# 411Level1.net
KiCad netlist of a schematic drawn in EAGLE
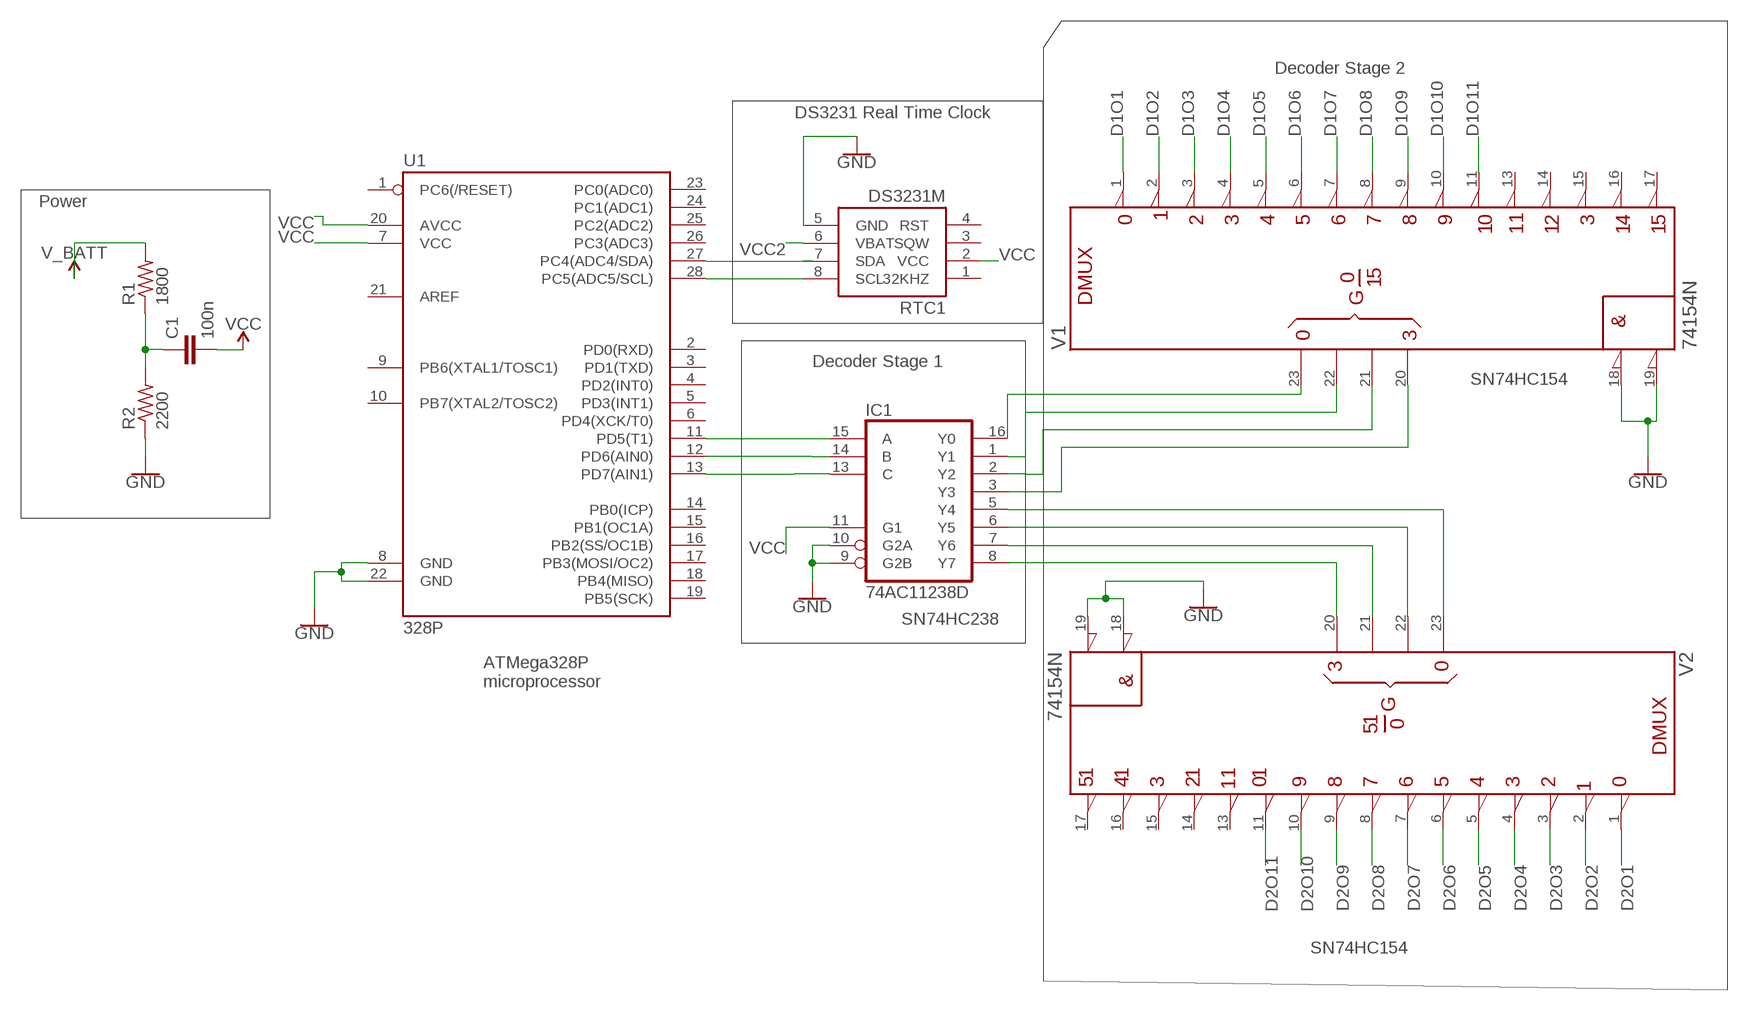
[diagram p0: schematic, sheet 1]
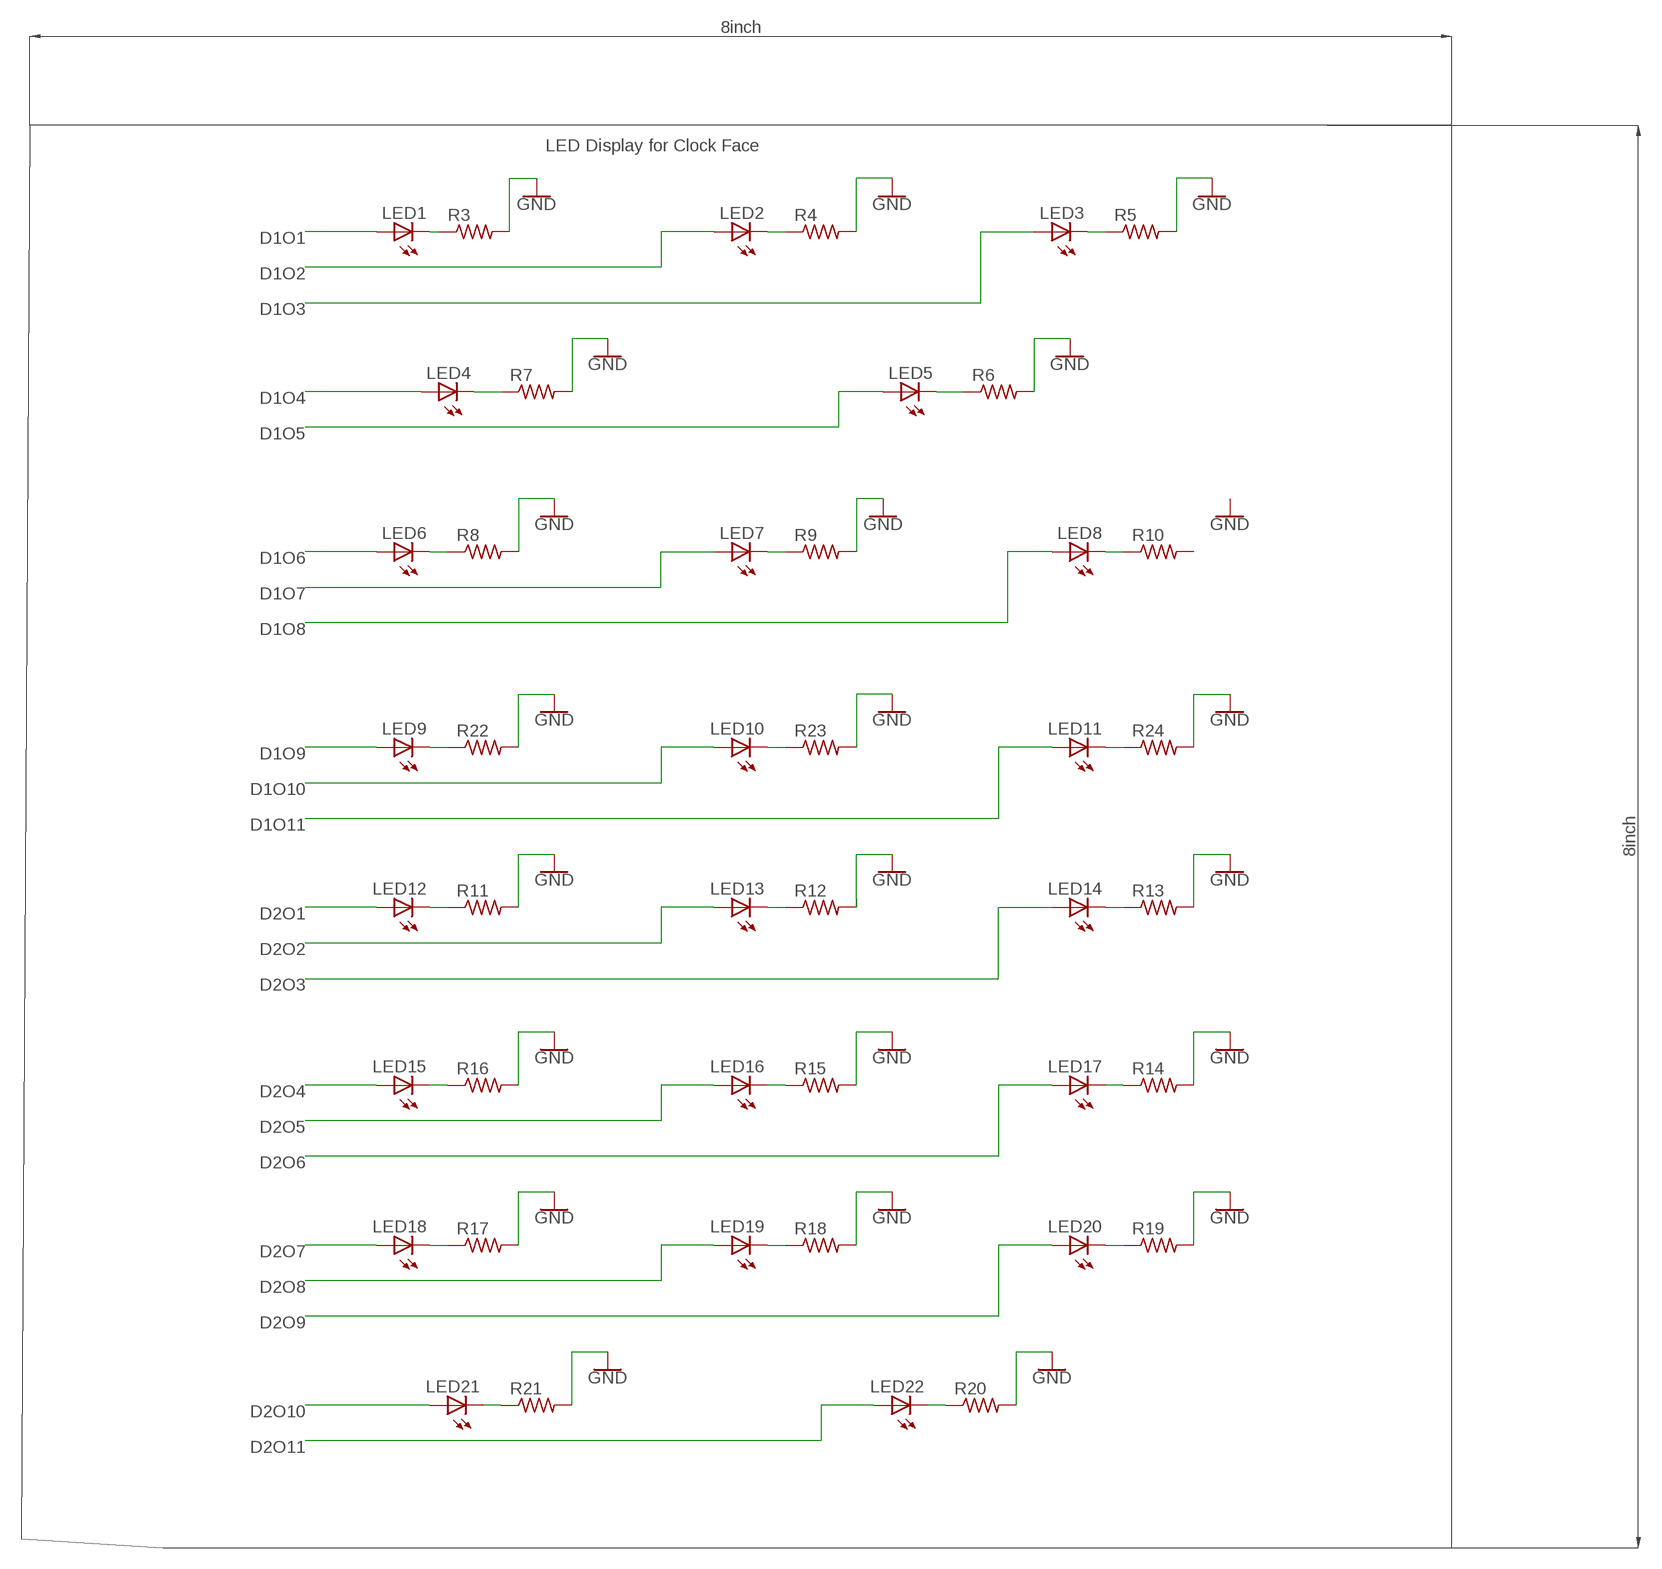
[diagram p1: schematic, sheet 2]

(export (version "E")
  (design (tool "Eeschema 10.0.6"))
  (components
    (comp (ref "C1")
      (value "100n")
      (footprint "eagle-import:C025-025X050")
      (libsource (lib "eagle-import") (part "C-EU025-025X050"))
    )
    (comp (ref "IC1")
      (value "74AC11238D")
      (footprint "eagle-import:SO16")
      (libsource (lib "eagle-import") (part "74AC11238D"))
    )
    (comp (ref "R1")
      (value "1800")
      (footprint "eagle-import:0204V")
      (libsource (lib "eagle-import") (part "R-US_0204/2V"))
    )
    (comp (ref "R2")
      (value "2200")
      (footprint "eagle-import:0204V")
      (libsource (lib "eagle-import") (part "R-US_0204/2V"))
    )
    (comp (ref "RTC1")
      (value "DS3231M")
      (footprint "eagle-import:SO08")
      (libsource (lib "eagle-import") (part "DS3231M"))
    )
    (comp (ref "U1")
      (value "328P")
      (footprint "eagle-import:DIP28")
      (libsource (lib "eagle-import") (part "ATMEGA328P_PDIP"))
    )
    (comp (ref "V1")
      (value "74154N")
      (footprint "eagle-import:DIL24-3")
      (libsource (lib "eagle-import") (part "74154N"))
    )
    (comp (ref "V2")
      (value "74154N")
      (footprint "eagle-import:DIL24-3")
      (libsource (lib "eagle-import") (part "74154N"))
    )
    (comp (ref "LED1")
      (value "LED5MM")
      (footprint "eagle-import:LED5MM")
      (libsource (lib "eagle-import") (part "LED5MM"))
    )
    (comp (ref "LED2")
      (value "LED5MM")
      (footprint "eagle-import:LED5MM")
      (libsource (lib "eagle-import") (part "LED5MM"))
    )
    (comp (ref "LED3")
      (value "LED5MM")
      (footprint "eagle-import:LED5MM")
      (libsource (lib "eagle-import") (part "LED5MM"))
    )
    (comp (ref "LED4")
      (value "LED5MM")
      (footprint "eagle-import:LED5MM")
      (libsource (lib "eagle-import") (part "LED5MM"))
    )
    (comp (ref "LED5")
      (value "LED5MM")
      (footprint "eagle-import:LED5MM")
      (libsource (lib "eagle-import") (part "LED5MM"))
    )
    (comp (ref "LED6")
      (value "LED5MM")
      (footprint "eagle-import:LED5MM")
      (libsource (lib "eagle-import") (part "LED5MM"))
    )
    (comp (ref "LED7")
      (value "LED5MM")
      (footprint "eagle-import:LED5MM")
      (libsource (lib "eagle-import") (part "LED5MM"))
    )
    (comp (ref "LED8")
      (value "LED5MM")
      (footprint "eagle-import:LED5MM")
      (libsource (lib "eagle-import") (part "LED5MM"))
    )
    (comp (ref "LED9")
      (value "LED5MM")
      (footprint "eagle-import:LED5MM")
      (libsource (lib "eagle-import") (part "LED5MM"))
    )
    (comp (ref "LED10")
      (value "LED5MM")
      (footprint "eagle-import:LED5MM")
      (libsource (lib "eagle-import") (part "LED5MM"))
    )
    (comp (ref "LED11")
      (value "LED5MM")
      (footprint "eagle-import:LED5MM")
      (libsource (lib "eagle-import") (part "LED5MM"))
    )
    (comp (ref "LED12")
      (value "LED5MM")
      (footprint "eagle-import:LED5MM")
      (libsource (lib "eagle-import") (part "LED5MM"))
    )
    (comp (ref "LED13")
      (value "LED5MM")
      (footprint "eagle-import:LED5MM")
      (libsource (lib "eagle-import") (part "LED5MM"))
    )
    (comp (ref "LED14")
      (value "LED5MM")
      (footprint "eagle-import:LED5MM")
      (libsource (lib "eagle-import") (part "LED5MM"))
    )
    (comp (ref "LED15")
      (value "LED5MM")
      (footprint "eagle-import:LED5MM")
      (libsource (lib "eagle-import") (part "LED5MM"))
    )
    (comp (ref "LED16")
      (value "LED5MM")
      (footprint "eagle-import:LED5MM")
      (libsource (lib "eagle-import") (part "LED5MM"))
    )
    (comp (ref "LED17")
      (value "LED5MM")
      (footprint "eagle-import:LED5MM")
      (libsource (lib "eagle-import") (part "LED5MM"))
    )
    (comp (ref "LED18")
      (value "LED5MM")
      (footprint "eagle-import:LED5MM")
      (libsource (lib "eagle-import") (part "LED5MM"))
    )
    (comp (ref "LED19")
      (value "LED5MM")
      (footprint "eagle-import:LED5MM")
      (libsource (lib "eagle-import") (part "LED5MM"))
    )
    (comp (ref "LED20")
      (value "LED5MM")
      (footprint "eagle-import:LED5MM")
      (libsource (lib "eagle-import") (part "LED5MM"))
    )
    (comp (ref "LED21")
      (value "LED5MM")
      (footprint "eagle-import:LED5MM")
      (libsource (lib "eagle-import") (part "LED5MM"))
    )
    (comp (ref "LED22")
      (value "LED5MM")
      (footprint "eagle-import:LED5MM")
      (libsource (lib "eagle-import") (part "LED5MM"))
    )
    (comp (ref "R3")
      (value "R-US_0204/5")
      (footprint "eagle-import:0204_5")
      (libsource (lib "eagle-import") (part "R-US_0204/5"))
    )
    (comp (ref "R4")
      (value "R-US_0204/5")
      (footprint "eagle-import:0204_5")
      (libsource (lib "eagle-import") (part "R-US_0204/5"))
    )
    (comp (ref "R5")
      (value "R-US_0204/5")
      (footprint "eagle-import:0204_5")
      (libsource (lib "eagle-import") (part "R-US_0204/5"))
    )
    (comp (ref "R6")
      (value "R-US_0204/5")
      (footprint "eagle-import:0204_5")
      (libsource (lib "eagle-import") (part "R-US_0204/5"))
    )
    (comp (ref "R7")
      (value "R-US_0204/5")
      (footprint "eagle-import:0204_5")
      (libsource (lib "eagle-import") (part "R-US_0204/5"))
    )
    (comp (ref "R8")
      (value "R-US_0204/5")
      (footprint "eagle-import:0204_5")
      (libsource (lib "eagle-import") (part "R-US_0204/5"))
    )
    (comp (ref "R9")
      (value "R-US_0204/5")
      (footprint "eagle-import:0204_5")
      (libsource (lib "eagle-import") (part "R-US_0204/5"))
    )
    (comp (ref "R10")
      (value "R-US_0204/5")
      (footprint "eagle-import:0204_5")
      (libsource (lib "eagle-import") (part "R-US_0204/5"))
    )
    (comp (ref "R11")
      (value "R-US_0204/5")
      (footprint "eagle-import:0204_5")
      (libsource (lib "eagle-import") (part "R-US_0204/5"))
    )
    (comp (ref "R12")
      (value "R-US_0204/5")
      (footprint "eagle-import:0204_5")
      (libsource (lib "eagle-import") (part "R-US_0204/5"))
    )
    (comp (ref "R13")
      (value "R-US_0204/5")
      (footprint "eagle-import:0204_5")
      (libsource (lib "eagle-import") (part "R-US_0204/5"))
    )
    (comp (ref "R14")
      (value "R-US_0204/5")
      (footprint "eagle-import:0204_5")
      (libsource (lib "eagle-import") (part "R-US_0204/5"))
    )
    (comp (ref "R15")
      (value "R-US_0204/5")
      (footprint "eagle-import:0204_5")
      (libsource (lib "eagle-import") (part "R-US_0204/5"))
    )
    (comp (ref "R16")
      (value "R-US_0204/5")
      (footprint "eagle-import:0204_5")
      (libsource (lib "eagle-import") (part "R-US_0204/5"))
    )
    (comp (ref "R17")
      (value "R-US_0204/5")
      (footprint "eagle-import:0204_5")
      (libsource (lib "eagle-import") (part "R-US_0204/5"))
    )
    (comp (ref "R18")
      (value "R-US_0204/5")
      (footprint "eagle-import:0204_5")
      (libsource (lib "eagle-import") (part "R-US_0204/5"))
    )
    (comp (ref "R19")
      (value "R-US_0204/5")
      (footprint "eagle-import:0204_5")
      (libsource (lib "eagle-import") (part "R-US_0204/5"))
    )
    (comp (ref "R20")
      (value "R-US_0204/5")
      (footprint "eagle-import:0204_5")
      (libsource (lib "eagle-import") (part "R-US_0204/5"))
    )
    (comp (ref "R21")
      (value "R-US_0204/5")
      (footprint "eagle-import:0204_5")
      (libsource (lib "eagle-import") (part "R-US_0204/5"))
    )
    (comp (ref "R22")
      (value "R-US_0204/5")
      (footprint "eagle-import:0204_5")
      (libsource (lib "eagle-import") (part "R-US_0204/5"))
    )
    (comp (ref "R23")
      (value "R-US_0204/5")
      (footprint "eagle-import:0204_5")
      (libsource (lib "eagle-import") (part "R-US_0204/5"))
    )
    (comp (ref "R24")
      (value "R-US_0204/5")
      (footprint "eagle-import:0204_5")
      (libsource (lib "eagle-import") (part "R-US_0204/5"))
    )
  )
  (nets
    (net (code "1") (name "D1O1") (class "Default")
      (node (ref "LED1") (pin "A") (pinfunction "A_A") (pintype "passive"))
      (node (ref "V1") (pin "1") (pinfunction "0_1") (pintype "output"))
    )
    (net (code "2") (name "D1O2") (class "Default")
      (node (ref "LED2") (pin "A") (pinfunction "A_A") (pintype "passive"))
      (node (ref "V1") (pin "2") (pinfunction "1_2") (pintype "output"))
    )
    (net (code "3") (name "D1O3") (class "Default")
      (node (ref "LED3") (pin "A") (pinfunction "A_A") (pintype "passive"))
      (node (ref "V1") (pin "3") (pinfunction "2_3") (pintype "output"))
    )
    (net (code "4") (name "D1O4") (class "Default")
      (node (ref "LED4") (pin "A") (pinfunction "A_A") (pintype "passive"))
      (node (ref "V1") (pin "4") (pinfunction "3_4") (pintype "output"))
    )
    (net (code "5") (name "D1O5") (class "Default")
      (node (ref "LED5") (pin "A") (pinfunction "A_A") (pintype "passive"))
      (node (ref "V1") (pin "5") (pinfunction "4_5") (pintype "output"))
    )
    (net (code "6") (name "D1O6") (class "Default")
      (node (ref "LED6") (pin "A") (pinfunction "A_A") (pintype "passive"))
      (node (ref "V1") (pin "6") (pinfunction "5_6") (pintype "output"))
    )
    (net (code "7") (name "D1O7") (class "Default")
      (node (ref "LED7") (pin "A") (pinfunction "A_A") (pintype "passive"))
      (node (ref "V1") (pin "7") (pinfunction "6_7") (pintype "output"))
    )
    (net (code "8") (name "D1O8") (class "Default")
      (node (ref "LED8") (pin "A") (pinfunction "A_A") (pintype "passive"))
      (node (ref "V1") (pin "8") (pinfunction "7_8") (pintype "output"))
    )
    (net (code "9") (name "D1O9") (class "Default")
      (node (ref "LED9") (pin "A") (pinfunction "A_A") (pintype "passive"))
      (node (ref "V1") (pin "9") (pinfunction "8_9") (pintype "output"))
    )
    (net (code "10") (name "D1O10") (class "Default")
      (node (ref "LED10") (pin "A") (pinfunction "A_A") (pintype "passive"))
      (node (ref "V1") (pin "10") (pinfunction "9_10") (pintype "output"))
    )
    (net (code "11") (name "D1O11") (class "Default")
      (node (ref "LED11") (pin "A") (pinfunction "A_A") (pintype "passive"))
      (node (ref "V1") (pin "11") (pinfunction "10_11") (pintype "output"))
    )
    (net (code "12") (name "D2O1") (class "Default")
      (node (ref "LED12") (pin "A") (pinfunction "A_A") (pintype "passive"))
      (node (ref "V2") (pin "1") (pinfunction "0_1") (pintype "output"))
    )
    (net (code "13") (name "D2O2") (class "Default")
      (node (ref "LED13") (pin "A") (pinfunction "A_A") (pintype "passive"))
      (node (ref "V2") (pin "2") (pinfunction "1_2") (pintype "output"))
    )
    (net (code "14") (name "D2O3") (class "Default")
      (node (ref "LED14") (pin "A") (pinfunction "A_A") (pintype "passive"))
      (node (ref "V2") (pin "3") (pinfunction "2_3") (pintype "output"))
    )
    (net (code "15") (name "D2O4") (class "Default")
      (node (ref "LED15") (pin "A") (pinfunction "A_A") (pintype "passive"))
      (node (ref "V2") (pin "4") (pinfunction "3_4") (pintype "output"))
    )
    (net (code "16") (name "D2O5") (class "Default")
      (node (ref "LED16") (pin "A") (pinfunction "A_A") (pintype "passive"))
      (node (ref "V2") (pin "5") (pinfunction "4_5") (pintype "output"))
    )
    (net (code "17") (name "D2O6") (class "Default")
      (node (ref "LED17") (pin "A") (pinfunction "A_A") (pintype "passive"))
      (node (ref "V2") (pin "6") (pinfunction "5_6") (pintype "output"))
    )
    (net (code "18") (name "D2O7") (class "Default")
      (node (ref "LED18") (pin "A") (pinfunction "A_A") (pintype "passive"))
      (node (ref "V2") (pin "7") (pinfunction "6_7") (pintype "output"))
    )
    (net (code "19") (name "D2O8") (class "Default")
      (node (ref "LED19") (pin "A") (pinfunction "A_A") (pintype "passive"))
      (node (ref "V2") (pin "8") (pinfunction "7_8") (pintype "output"))
    )
    (net (code "20") (name "D2O9") (class "Default")
      (node (ref "LED20") (pin "A") (pinfunction "A_A") (pintype "passive"))
      (node (ref "V2") (pin "9") (pinfunction "8_9") (pintype "output"))
    )
    (net (code "21") (name "D2O10") (class "Default")
      (node (ref "LED21") (pin "A") (pinfunction "A_A") (pintype "passive"))
      (node (ref "V2") (pin "10") (pinfunction "9_10") (pintype "output"))
    )
    (net (code "22") (name "D2O11") (class "Default")
      (node (ref "LED22") (pin "A") (pinfunction "A_A") (pintype "passive"))
      (node (ref "V2") (pin "11") (pinfunction "10_11") (pintype "output"))
    )
    (net (code "23") (name "GND") (class "Default")
      (node (ref "IC1") (pin "10") (pinfunction "G2A_10") (pintype "input"))
      (node (ref "IC1") (pin "9") (pinfunction "G2B_9") (pintype "input"))
      (node (ref "R11") (pin "2") (pinfunction "2_2") (pintype "passive"))
      (node (ref "R12") (pin "2") (pinfunction "2_2") (pintype "passive"))
      (node (ref "R13") (pin "2") (pinfunction "2_2") (pintype "passive"))
      (node (ref "R14") (pin "2") (pinfunction "2_2") (pintype "passive"))
      (node (ref "R15") (pin "2") (pinfunction "2_2") (pintype "passive"))
      (node (ref "R16") (pin "2") (pinfunction "2_2") (pintype "passive"))
      (node (ref "R17") (pin "2") (pinfunction "2_2") (pintype "passive"))
      (node (ref "R18") (pin "2") (pinfunction "2_2") (pintype "passive"))
      (node (ref "R19") (pin "2") (pinfunction "2_2") (pintype "passive"))
      (node (ref "R2") (pin "1") (pinfunction "1_1") (pintype "passive"))
      (node (ref "R20") (pin "2") (pinfunction "2_2") (pintype "passive"))
      (node (ref "R21") (pin "2") (pinfunction "2_2") (pintype "passive"))
      (node (ref "R22") (pin "2") (pinfunction "2_2") (pintype "passive"))
      (node (ref "R23") (pin "2") (pinfunction "2_2") (pintype "passive"))
      (node (ref "R24") (pin "2") (pinfunction "2_2") (pintype "passive"))
      (node (ref "R3") (pin "2") (pinfunction "2_2") (pintype "passive"))
      (node (ref "R4") (pin "2") (pinfunction "2_2") (pintype "passive"))
      (node (ref "R5") (pin "2") (pinfunction "2_2") (pintype "passive"))
      (node (ref "R6") (pin "2") (pinfunction "2_2") (pintype "passive"))
      (node (ref "R7") (pin "2") (pinfunction "2_2") (pintype "passive"))
      (node (ref "R8") (pin "2") (pinfunction "2_2") (pintype "passive"))
      (node (ref "R9") (pin "2") (pinfunction "2_2") (pintype "passive"))
      (node (ref "RTC1") (pin "5") (pinfunction "GND_5") (pintype "power_in"))
      (node (ref "U1") (pin "22") (pinfunction "GND_22") (pintype "bidirectional"))
      (node (ref "U1") (pin "8") (pinfunction "GND_8") (pintype "bidirectional"))
      (node (ref "V1") (pin "18") (pinfunction "~{G1}_18") (pintype "input"))
      (node (ref "V1") (pin "19") (pinfunction "~{G2}_19") (pintype "input"))
      (node (ref "V2") (pin "18") (pinfunction "~{G1}_18") (pintype "input"))
      (node (ref "V2") (pin "19") (pinfunction "~{G2}_19") (pintype "input"))
    )
    (net (code "24") (name "Net-(C1-Pad1)") (class "Default")
      (node (ref "C1") (pin "1") (pinfunction "1_1") (pintype "passive"))
      (node (ref "R1") (pin "1") (pinfunction "1_1") (pintype "passive"))
      (node (ref "R2") (pin "2") (pinfunction "2_2") (pintype "passive"))
    )
    (net (code "25") (name "Net-(IC1A-A)") (class "Default")
      (node (ref "IC1") (pin "15") (pinfunction "A_15") (pintype "input"))
      (node (ref "U1") (pin "11") (pinfunction "PD5(T1)_11") (pintype "bidirectional"))
    )
    (net (code "26") (name "Net-(IC1A-B)") (class "Default")
      (node (ref "IC1") (pin "14") (pinfunction "B_14") (pintype "input"))
      (node (ref "U1") (pin "12") (pinfunction "PD6(AIN0)_12") (pintype "bidirectional"))
    )
    (net (code "27") (name "Net-(IC1A-C)") (class "Default")
      (node (ref "IC1") (pin "13") (pinfunction "C_13") (pintype "input"))
      (node (ref "U1") (pin "13") (pinfunction "PD7(AIN1)_13") (pintype "bidirectional"))
    )
    (net (code "28") (name "Net-(IC1A-Y0)") (class "Default")
      (node (ref "IC1") (pin "16") (pinfunction "Y0_16") (pintype "output"))
      (node (ref "V1") (pin "23") (pinfunction "A_23") (pintype "input"))
    )
    (net (code "29") (name "Net-(IC1A-Y1)") (class "Default")
      (node (ref "IC1") (pin "1") (pinfunction "Y1_1") (pintype "output"))
      (node (ref "V1") (pin "22") (pinfunction "B_22") (pintype "input"))
    )
    (net (code "30") (name "Net-(IC1A-Y2)") (class "Default")
      (node (ref "IC1") (pin "2") (pinfunction "Y2_2") (pintype "output"))
      (node (ref "V1") (pin "21") (pinfunction "C_21") (pintype "input"))
    )
    (net (code "31") (name "Net-(IC1A-Y3)") (class "Default")
      (node (ref "IC1") (pin "3") (pinfunction "Y3_3") (pintype "output"))
      (node (ref "V1") (pin "20") (pinfunction "D_20") (pintype "input"))
    )
    (net (code "32") (name "Net-(IC1A-Y4)") (class "Default")
      (node (ref "IC1") (pin "5") (pinfunction "Y4_5") (pintype "output"))
      (node (ref "V2") (pin "23") (pinfunction "A_23") (pintype "input"))
    )
    (net (code "33") (name "Net-(IC1A-Y5)") (class "Default")
      (node (ref "IC1") (pin "6") (pinfunction "Y5_6") (pintype "output"))
      (node (ref "V2") (pin "22") (pinfunction "B_22") (pintype "input"))
    )
    (net (code "34") (name "Net-(IC1A-Y6)") (class "Default")
      (node (ref "IC1") (pin "7") (pinfunction "Y6_7") (pintype "output"))
      (node (ref "V2") (pin "21") (pinfunction "C_21") (pintype "input"))
    )
    (net (code "35") (name "Net-(IC1A-Y7)") (class "Default")
      (node (ref "IC1") (pin "8") (pinfunction "Y7_8") (pintype "output"))
      (node (ref "V2") (pin "20") (pinfunction "D_20") (pintype "input"))
    )
    (net (code "36") (name "Net-(LED1-C)") (class "Default")
      (node (ref "LED1") (pin "K") (pinfunction "C_K") (pintype "passive"))
      (node (ref "R3") (pin "1") (pinfunction "1_1") (pintype "passive"))
    )
    (net (code "37") (name "Net-(LED2-C)") (class "Default")
      (node (ref "LED2") (pin "K") (pinfunction "C_K") (pintype "passive"))
      (node (ref "R4") (pin "1") (pinfunction "1_1") (pintype "passive"))
    )
    (net (code "38") (name "Net-(LED3-C)") (class "Default")
      (node (ref "LED3") (pin "K") (pinfunction "C_K") (pintype "passive"))
      (node (ref "R5") (pin "1") (pinfunction "1_1") (pintype "passive"))
    )
    (net (code "39") (name "Net-(LED4-C)") (class "Default")
      (node (ref "LED4") (pin "K") (pinfunction "C_K") (pintype "passive"))
      (node (ref "R7") (pin "1") (pinfunction "1_1") (pintype "passive"))
    )
    (net (code "40") (name "Net-(LED5-C)") (class "Default")
      (node (ref "LED5") (pin "K") (pinfunction "C_K") (pintype "passive"))
      (node (ref "R6") (pin "1") (pinfunction "1_1") (pintype "passive"))
    )
    (net (code "41") (name "Net-(LED6-C)") (class "Default")
      (node (ref "LED6") (pin "K") (pinfunction "C_K") (pintype "passive"))
      (node (ref "R8") (pin "1") (pinfunction "1_1") (pintype "passive"))
    )
    (net (code "42") (name "Net-(LED7-C)") (class "Default")
      (node (ref "LED7") (pin "K") (pinfunction "C_K") (pintype "passive"))
      (node (ref "R9") (pin "1") (pinfunction "1_1") (pintype "passive"))
    )
    (net (code "43") (name "Net-(LED8-C)") (class "Default")
      (node (ref "LED8") (pin "K") (pinfunction "C_K") (pintype "passive"))
      (node (ref "R10") (pin "1") (pinfunction "1_1") (pintype "passive"))
    )
    (net (code "44") (name "Net-(LED9-C)") (class "Default")
      (node (ref "LED9") (pin "K") (pinfunction "C_K") (pintype "passive"))
      (node (ref "R22") (pin "1") (pinfunction "1_1") (pintype "passive"))
    )
    (net (code "45") (name "Net-(LED10-C)") (class "Default")
      (node (ref "LED10") (pin "K") (pinfunction "C_K") (pintype "passive"))
      (node (ref "R23") (pin "1") (pinfunction "1_1") (pintype "passive"))
    )
    (net (code "46") (name "Net-(LED11-C)") (class "Default")
      (node (ref "LED11") (pin "K") (pinfunction "C_K") (pintype "passive"))
      (node (ref "R24") (pin "1") (pinfunction "1_1") (pintype "passive"))
    )
    (net (code "47") (name "Net-(LED12-C)") (class "Default")
      (node (ref "LED12") (pin "K") (pinfunction "C_K") (pintype "passive"))
      (node (ref "R11") (pin "1") (pinfunction "1_1") (pintype "passive"))
    )
    (net (code "48") (name "Net-(LED13-C)") (class "Default")
      (node (ref "LED13") (pin "K") (pinfunction "C_K") (pintype "passive"))
      (node (ref "R12") (pin "1") (pinfunction "1_1") (pintype "passive"))
    )
    (net (code "49") (name "Net-(LED14-C)") (class "Default")
      (node (ref "LED14") (pin "K") (pinfunction "C_K") (pintype "passive"))
      (node (ref "R13") (pin "1") (pinfunction "1_1") (pintype "passive"))
    )
    (net (code "50") (name "Net-(LED15-C)") (class "Default")
      (node (ref "LED15") (pin "K") (pinfunction "C_K") (pintype "passive"))
      (node (ref "R16") (pin "1") (pinfunction "1_1") (pintype "passive"))
    )
    (net (code "51") (name "Net-(LED16-C)") (class "Default")
      (node (ref "LED16") (pin "K") (pinfunction "C_K") (pintype "passive"))
      (node (ref "R15") (pin "1") (pinfunction "1_1") (pintype "passive"))
    )
    (net (code "52") (name "Net-(LED17-C)") (class "Default")
      (node (ref "LED17") (pin "K") (pinfunction "C_K") (pintype "passive"))
      (node (ref "R14") (pin "1") (pinfunction "1_1") (pintype "passive"))
    )
    (net (code "53") (name "Net-(LED18-C)") (class "Default")
      (node (ref "LED18") (pin "K") (pinfunction "C_K") (pintype "passive"))
      (node (ref "R17") (pin "1") (pinfunction "1_1") (pintype "passive"))
    )
    (net (code "54") (name "Net-(LED19-C)") (class "Default")
      (node (ref "LED19") (pin "K") (pinfunction "C_K") (pintype "passive"))
      (node (ref "R18") (pin "1") (pinfunction "1_1") (pintype "passive"))
    )
    (net (code "55") (name "Net-(LED20-C)") (class "Default")
      (node (ref "LED20") (pin "K") (pinfunction "C_K") (pintype "passive"))
      (node (ref "R19") (pin "1") (pinfunction "1_1") (pintype "passive"))
    )
    (net (code "56") (name "Net-(LED21-C)") (class "Default")
      (node (ref "LED21") (pin "K") (pinfunction "C_K") (pintype "passive"))
      (node (ref "R21") (pin "1") (pinfunction "1_1") (pintype "passive"))
    )
    (net (code "57") (name "Net-(LED22-C)") (class "Default")
      (node (ref "LED22") (pin "K") (pinfunction "C_K") (pintype "passive"))
      (node (ref "R20") (pin "1") (pinfunction "1_1") (pintype "passive"))
    )
    (net (code "58") (name "Net-(RTC1-SCL)") (class "Default")
      (node (ref "RTC1") (pin "8") (pinfunction "SCL_8") (pintype "bidirectional"))
      (node (ref "U1") (pin "28") (pinfunction "PC5(ADC5/SCL)_28") (pintype "bidirectional"))
    )
    (net (code "59") (name "Net-(RTC1-SDA)") (class "Default")
      (node (ref "RTC1") (pin "7") (pinfunction "SDA_7") (pintype "bidirectional"))
      (node (ref "U1") (pin "27") (pinfunction "PC4(ADC4/SDA)_27") (pintype "bidirectional"))
    )
    (net (code "60") (name "VCC") (class "Default")
      (node (ref "C1") (pin "2") (pinfunction "2_2") (pintype "passive"))
      (node (ref "IC1") (pin "11") (pinfunction "G1_11") (pintype "input"))
      (node (ref "RTC1") (pin "2") (pinfunction "VCC_2") (pintype "power_in"))
      (node (ref "U1") (pin "20") (pinfunction "AVCC_20") (pintype "bidirectional"))
      (node (ref "U1") (pin "7") (pinfunction "VCC_7") (pintype "bidirectional"))
    )
    (net (code "61") (name "VCC2") (class "Default")
      (node (ref "RTC1") (pin "6") (pinfunction "VBAT_6") (pintype "power_in"))
    )
    (net (code "62") (name "V_BATT") (class "Default")
      (node (ref "R1") (pin "2") (pinfunction "2_2") (pintype "passive"))
    )
    (net (code "63") (name "unconnected-(R10-Pad2)") (class "Default")
      (node (ref "R10") (pin "2") (pinfunction "2_2") (pintype "passive"))
    )
    (net (code "64") (name "unconnected-(RTC1-32KHZ-Pad1)") (class "Default")
      (node (ref "RTC1") (pin "1") (pinfunction "32KHZ_1") (pintype "output"))
    )
    (net (code "65") (name "unconnected-(RTC1-RST-Pad4)") (class "Default")
      (node (ref "RTC1") (pin "4") (pinfunction "RST_4") (pintype "bidirectional"))
    )
    (net (code "66") (name "unconnected-(RTC1-SQW-Pad3)") (class "Default")
      (node (ref "RTC1") (pin "3") (pinfunction "SQW_3") (pintype "output"))
    )
    (net (code "67") (name "unconnected-(U1-AREF-Pad21)") (class "Default")
      (node (ref "U1") (pin "21") (pinfunction "AREF_21") (pintype "bidirectional"))
    )
    (net (code "68") (name "unconnected-(U1-PB0(ICP)-Pad14)") (class "Default")
      (node (ref "U1") (pin "14") (pinfunction "PB0(ICP)_14") (pintype "bidirectional"))
    )
    (net (code "69") (name "unconnected-(U1-PB1(OC1A)-Pad15)") (class "Default")
      (node (ref "U1") (pin "15") (pinfunction "PB1(OC1A)_15") (pintype "bidirectional"))
    )
    (net (code "70") (name "unconnected-(U1-PB2(SS{slash}OC1B)-Pad16)") (class "Default")
      (node (ref "U1") (pin "16") (pinfunction "PB2(SS/OC1B)_16") (pintype "bidirectional"))
    )
    (net (code "71") (name "unconnected-(U1-PB3(MOSI{slash}OC2)-Pad17)") (class "Default")
      (node (ref "U1") (pin "17") (pinfunction "PB3(MOSI/OC2)_17") (pintype "bidirectional"))
    )
    (net (code "72") (name "unconnected-(U1-PB4(MISO)-Pad18)") (class "Default")
      (node (ref "U1") (pin "18") (pinfunction "PB4(MISO)_18") (pintype "bidirectional"))
    )
    (net (code "73") (name "unconnected-(U1-PB5(SCK)-Pad19)") (class "Default")
      (node (ref "U1") (pin "19") (pinfunction "PB5(SCK)_19") (pintype "bidirectional"))
    )
    (net (code "74") (name "unconnected-(U1-PB6(XTAL1{slash}TOSC1)-Pad9)") (class "Default")
      (node (ref "U1") (pin "9") (pinfunction "PB6(XTAL1/TOSC1)_9") (pintype "bidirectional"))
    )
    (net (code "75") (name "unconnected-(U1-PB7(XTAL2{slash}TOSC2)-Pad10)") (class "Default")
      (node (ref "U1") (pin "10") (pinfunction "PB7(XTAL2/TOSC2)_10") (pintype "bidirectional"))
    )
    (net (code "76") (name "unconnected-(U1-PC0(ADC0)-Pad23)") (class "Default")
      (node (ref "U1") (pin "23") (pinfunction "PC0(ADC0)_23") (pintype "bidirectional"))
    )
    (net (code "77") (name "unconnected-(U1-PC1(ADC1)-Pad24)") (class "Default")
      (node (ref "U1") (pin "24") (pinfunction "PC1(ADC1)_24") (pintype "bidirectional"))
    )
    (net (code "78") (name "unconnected-(U1-PC2(ADC2)-Pad25)") (class "Default")
      (node (ref "U1") (pin "25") (pinfunction "PC2(ADC2)_25") (pintype "bidirectional"))
    )
    (net (code "79") (name "unconnected-(U1-PC3(ADC3)-Pad26)") (class "Default")
      (node (ref "U1") (pin "26") (pinfunction "PC3(ADC3)_26") (pintype "bidirectional"))
    )
    (net (code "80") (name "unconnected-(U1-PC6({slash}RESET)-Pad1)") (class "Default")
      (node (ref "U1") (pin "1") (pinfunction "PC6(/RESET)_1") (pintype "bidirectional"))
    )
    (net (code "81") (name "unconnected-(U1-PD0(RXD)-Pad2)") (class "Default")
      (node (ref "U1") (pin "2") (pinfunction "PD0(RXD)_2") (pintype "bidirectional"))
    )
    (net (code "82") (name "unconnected-(U1-PD1(TXD)-Pad3)") (class "Default")
      (node (ref "U1") (pin "3") (pinfunction "PD1(TXD)_3") (pintype "bidirectional"))
    )
    (net (code "83") (name "unconnected-(U1-PD2(INT0)-Pad4)") (class "Default")
      (node (ref "U1") (pin "4") (pinfunction "PD2(INT0)_4") (pintype "bidirectional"))
    )
    (net (code "84") (name "unconnected-(U1-PD3(INT1)-Pad5)") (class "Default")
      (node (ref "U1") (pin "5") (pinfunction "PD3(INT1)_5") (pintype "bidirectional"))
    )
    (net (code "85") (name "unconnected-(U1-PD4(XCK{slash}T0)-Pad6)") (class "Default")
      (node (ref "U1") (pin "6") (pinfunction "PD4(XCK/T0)_6") (pintype "bidirectional"))
    )
    (net (code "86") (name "unconnected-(V1C-11-Pad13)") (class "Default")
      (node (ref "V1") (pin "13") (pinfunction "11_13") (pintype "output"))
    )
    (net (code "87") (name "unconnected-(V1C-12-Pad14)") (class "Default")
      (node (ref "V1") (pin "14") (pinfunction "12_14") (pintype "output"))
    )
    (net (code "88") (name "unconnected-(V1C-13-Pad15)") (class "Default")
      (node (ref "V1") (pin "15") (pinfunction "13_15") (pintype "output"))
    )
    (net (code "89") (name "unconnected-(V1C-14-Pad16)") (class "Default")
      (node (ref "V1") (pin "16") (pinfunction "14_16") (pintype "output"))
    )
    (net (code "90") (name "unconnected-(V1C-15-Pad17)") (class "Default")
      (node (ref "V1") (pin "17") (pinfunction "15_17") (pintype "output"))
    )
    (net (code "91") (name "unconnected-(V2C-11-Pad13)") (class "Default")
      (node (ref "V2") (pin "13") (pinfunction "11_13") (pintype "output"))
    )
    (net (code "92") (name "unconnected-(V2C-12-Pad14)") (class "Default")
      (node (ref "V2") (pin "14") (pinfunction "12_14") (pintype "output"))
    )
    (net (code "93") (name "unconnected-(V2C-13-Pad15)") (class "Default")
      (node (ref "V2") (pin "15") (pinfunction "13_15") (pintype "output"))
    )
    (net (code "94") (name "unconnected-(V2C-14-Pad16)") (class "Default")
      (node (ref "V2") (pin "16") (pinfunction "14_16") (pintype "output"))
    )
    (net (code "95") (name "unconnected-(V2C-15-Pad17)") (class "Default")
      (node (ref "V2") (pin "17") (pinfunction "15_17") (pintype "output"))
    )
  )
)
